# display_reva.net
KiCad netlist of a schematic drawn in EAGLE
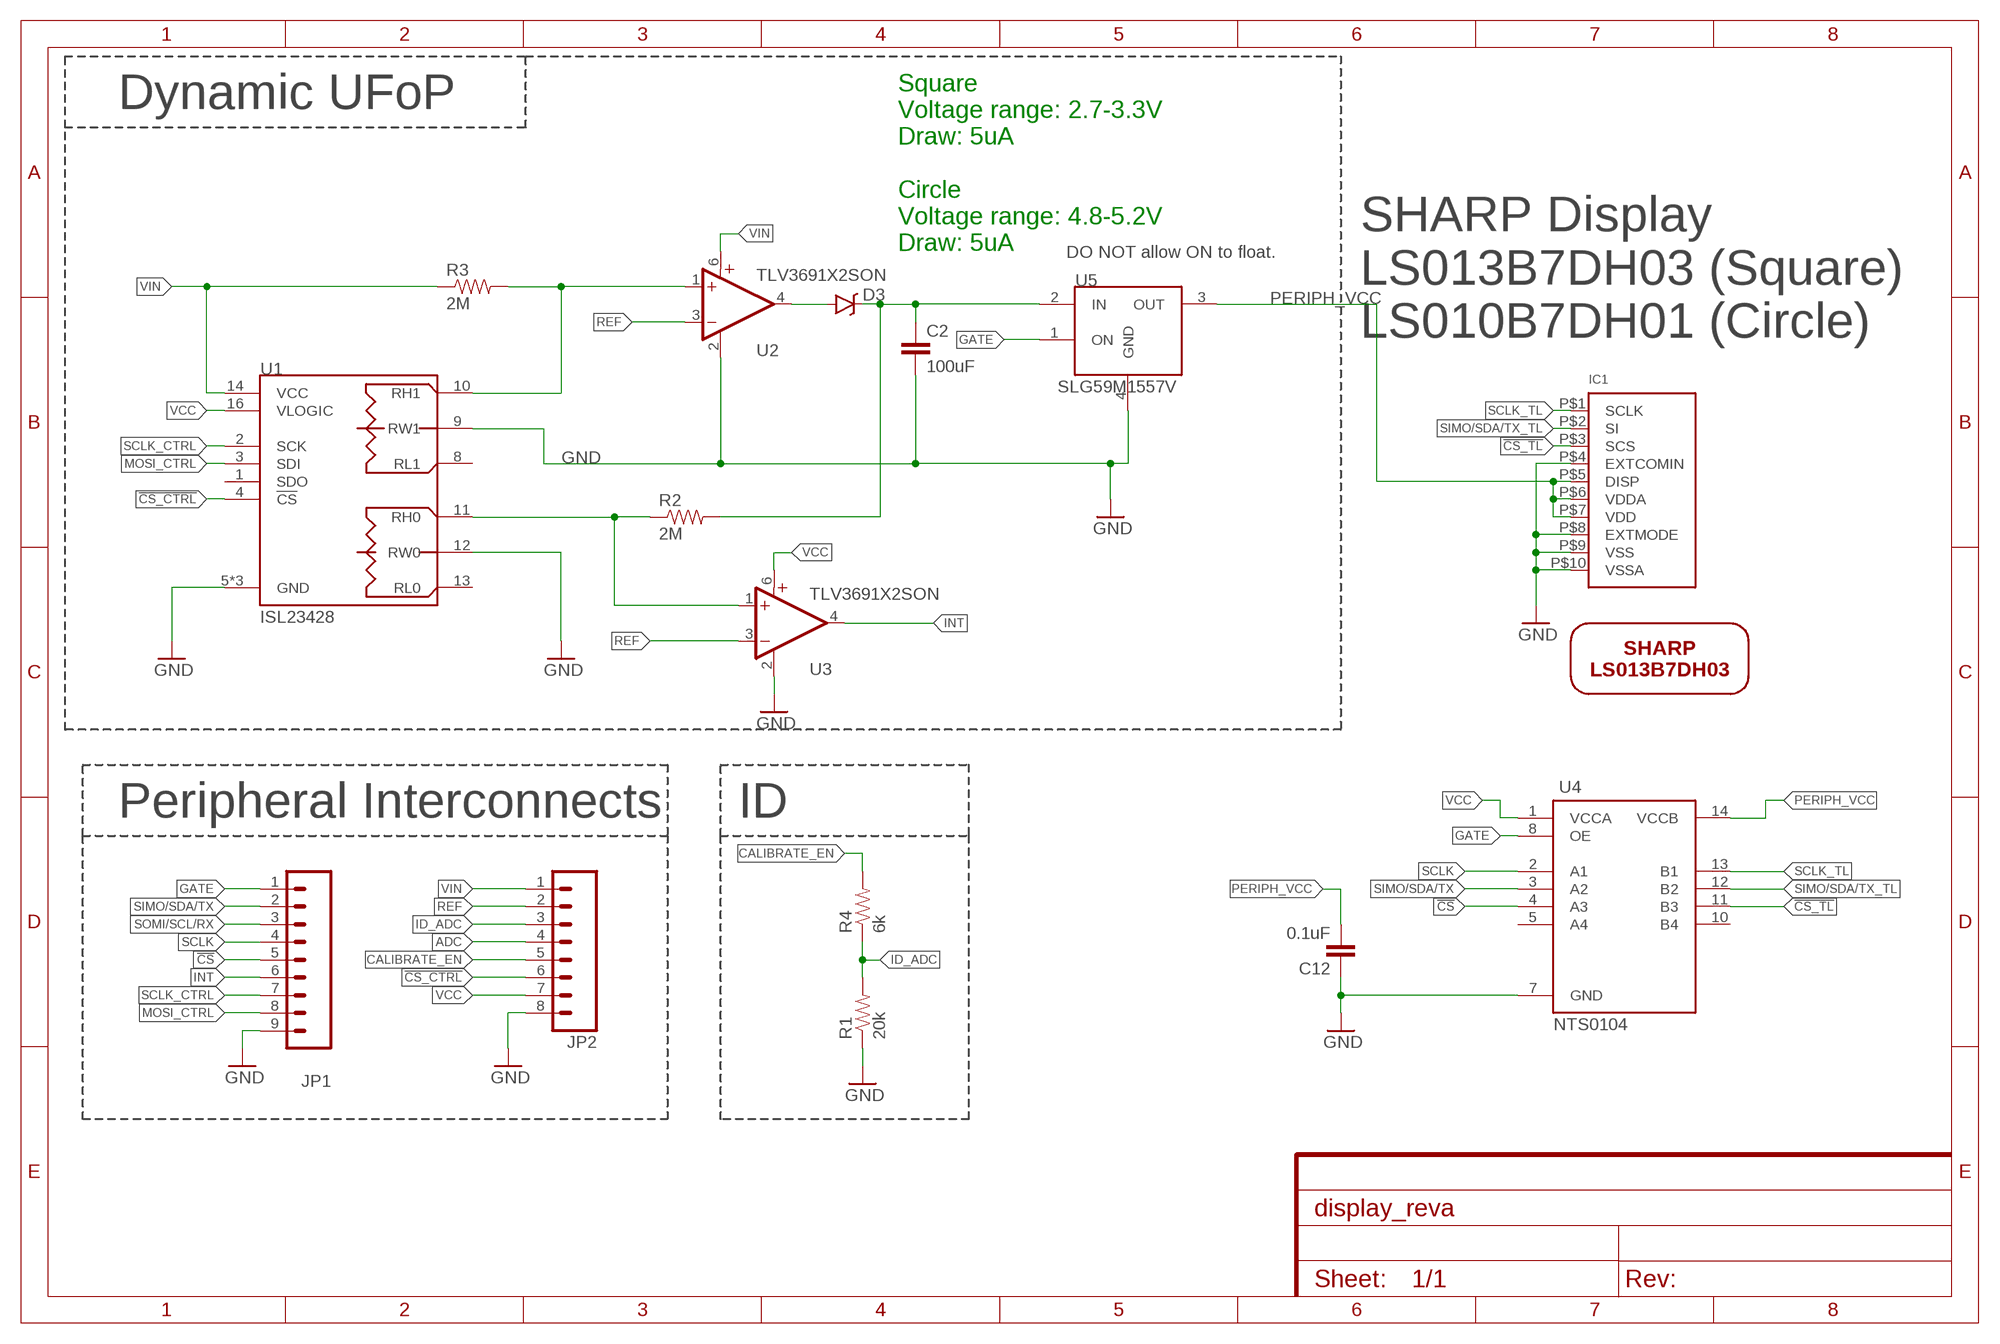
[diagram p0: schematic, sheet 1]

(export (version "E")
  (design (tool "Eeschema 10.0.6"))
  (components
    (comp (ref "C2")
      (value "100uF")
      (footprint "eagle-import:1206")
      (fields (field (name "MPN") "GRM31CR60J107ME39K"))
      (libsource (lib "eagle-import") (part "CAP1206"))
    )
    (comp (ref "C12")
      (value "0.1uF")
      (footprint "eagle-import:0402")
      (fields (field (name "MPN") "0402YD104KAT2A"))
      (libsource (lib "eagle-import") (part "C-EU"))
    )
    (comp (ref "D3")
      (value "RB751")
      (footprint "eagle-import:SOD-523")
      (fields (field (name "MPN") "BAS40-02V-V-G-08"))
      (libsource (lib "eagle-import") (part "DIODE-SCHOTTKY-RB751"))
    )
    (comp (ref "IC1")
      (value "SHARP_MEMORYLCD_10PIN")
      (footprint "eagle-import:FPC_10PIN_52892-1095")
      (fields (field (name "MPN") "0528921033"))
      (libsource (lib "eagle-import") (part "SHARP_MEMORYLCD_10PIN"))
    )
    (comp (ref "JP1")
      (value "M091.27MM")
      (footprint "eagle-import:1X09-1.27MM")
      (fields (field (name "MPN") "GRPB091VWVN-RC "))
      (libsource (lib "eagle-import") (part "M091.27MM"))
    )
    (comp (ref "JP2")
      (value "M081.27MM")
      (footprint "eagle-import:1X08-1.27MM")
      (fields (field (name "MPN") "GRPB081VWVN-RC "))
      (libsource (lib "eagle-import") (part "M081.27MM"))
    )
    (comp (ref "R1")
      (value "20k")
      (footprint "eagle-import:0402")
      (fields (field (name "MPN") "ERJ-2RKF2002X"))
      (libsource (lib "eagle-import") (part "R-EU"))
    )
    (comp (ref "R2")
      (value "2M")
      (footprint "eagle-import:0402")
      (fields (field (name "MPN") "RC1005F205CS"))
      (libsource (lib "eagle-import") (part "R-EU"))
    )
    (comp (ref "R3")
      (value "2M")
      (footprint "eagle-import:0402")
      (fields (field (name "MPN") "RC1005F205CS"))
      (libsource (lib "eagle-import") (part "R-EU"))
    )
    (comp (ref "R4")
      (value "6k")
      (footprint "eagle-import:0402")
      (fields (field (name "MPN") "RC0402FR-076K04L"))
      (libsource (lib "eagle-import") (part "R-EU"))
    )
    (comp (ref "U$3")
      (value "LS013B7DH03")
      (footprint "eagle-import:LS013B7DH03_HF")
      (libsource (lib "eagle-import") (part "LS013B7DH03"))
    )
    (comp (ref "U1")
      (value "ISL23428")
      (footprint "eagle-import:UTQFN-16")
      (fields (field (name "MPN") "ISL23428TFRUZ-T7A"))
      (libsource (lib "eagle-import") (part "ISL23428"))
    )
    (comp (ref "U2")
      (value "TLV3691X2SON")
      (footprint "eagle-import:X2SON")
      (fields (field (name "MPN") "TLV3691IDPFR"))
      (libsource (lib "eagle-import") (part "TLV3691X2SON"))
    )
    (comp (ref "U3")
      (value "TLV3691X2SON")
      (footprint "eagle-import:X2SON")
      (fields (field (name "MPN") "TLV3691IDPFR"))
      (libsource (lib "eagle-import") (part "TLV3691X2SON"))
    )
    (comp (ref "U4")
      (value "NTS0104")
      (footprint "eagle-import:TSSOP14")
      (fields (field (name "MANUFACTURERPARTNUMBER") "NTS0104PW,118 "))
      (libsource (lib "eagle-import") (part "NTS0104"))
    )
    (comp (ref "U5")
      (value "SLG59M1557V")
      (footprint "eagle-import:4STDFN")
      (fields (field (name "MPN") "SLG59M1557V "))
      (libsource (lib "eagle-import") (part "SLG59M1557V"))
    )
  )
  (nets
    (net (code "1") (name "/~{CS_CTRL}") (class "Default")
      (node (ref "JP2") (pin "6") (pinfunction "6_6") (pintype "passive"))
      (node (ref "U1") (pin "4") (pinfunction "~{CS}_4") (pintype "bidirectional"))
    )
    (net (code "2") (name "/~{CS_TL}") (class "Default")
      (node (ref "IC1") (pin "P$3") (pinfunction "SCS_P$3") (pintype "input"))
      (node (ref "U4") (pin "11") (pinfunction "B3_11") (pintype "bidirectional"))
    )
    (net (code "3") (name "/~{CS}") (class "Default")
      (node (ref "JP1") (pin "5") (pinfunction "5_5") (pintype "passive"))
      (node (ref "U4") (pin "4") (pinfunction "A3_4") (pintype "bidirectional"))
    )
    (net (code "4") (name "ADC") (class "Default")
      (node (ref "JP2") (pin "4") (pinfunction "4_4") (pintype "passive"))
    )
    (net (code "5") (name "CALIBRATE_EN") (class "Default")
      (node (ref "JP2") (pin "5") (pinfunction "5_5") (pintype "passive"))
      (node (ref "R4") (pin "2") (pinfunction "2_2") (pintype "passive"))
    )
    (net (code "6") (name "GATE") (class "Default")
      (node (ref "JP1") (pin "1") (pinfunction "1_1") (pintype "passive"))
      (node (ref "U4") (pin "8") (pinfunction "OE_8") (pintype "bidirectional"))
      (node (ref "U5") (pin "1") (pinfunction "ON_1") (pintype "bidirectional"))
    )
    (net (code "7") (name "GND") (class "Default")
      (node (ref "C12") (pin "1") (pinfunction "1_1") (pintype "passive"))
      (node (ref "C2") (pin "2") (pinfunction "2_2") (pintype "passive"))
      (node (ref "IC1") (pin "P$10") (pinfunction "VSSA_P$10") (pintype "power_in"))
      (node (ref "IC1") (pin "P$4") (pinfunction "EXTCOMIN_P$4") (pintype "input"))
      (node (ref "IC1") (pin "P$8") (pinfunction "EXTMODE_P$8") (pintype "input"))
      (node (ref "IC1") (pin "P$9") (pinfunction "VSS_P$9") (pintype "power_in"))
      (node (ref "JP1") (pin "9") (pinfunction "9_9") (pintype "passive"))
      (node (ref "JP2") (pin "8") (pinfunction "8_8") (pintype "passive"))
      (node (ref "R1") (pin "1") (pinfunction "1_1") (pintype "passive"))
      (node (ref "U1") (pin "12") (pinfunction "RW0_12") (pintype "bidirectional"))
      (node (ref "U1") (pin "15") (pinfunction "GND_15") (pintype "bidirectional"))
      (node (ref "U1") (pin "5") (pinfunction "GND_5") (pintype "bidirectional"))
      (node (ref "U1") (pin "6") (pinfunction "GND_6") (pintype "bidirectional"))
      (node (ref "U1") (pin "9") (pinfunction "RW1_9") (pintype "bidirectional"))
      (node (ref "U2") (pin "2") (pinfunction "GND_2") (pintype "power_in"))
      (node (ref "U3") (pin "2") (pinfunction "GND_2") (pintype "power_in"))
      (node (ref "U4") (pin "7") (pinfunction "GND_7") (pintype "bidirectional"))
      (node (ref "U5") (pin "4") (pinfunction "GND_4") (pintype "bidirectional"))
    )
    (net (code "8") (name "ID_ADC") (class "Default")
      (node (ref "JP2") (pin "3") (pinfunction "3_3") (pintype "passive"))
      (node (ref "R1") (pin "2") (pinfunction "2_2") (pintype "passive"))
      (node (ref "R4") (pin "1") (pinfunction "1_1") (pintype "passive"))
    )
    (net (code "9") (name "INT") (class "Default")
      (node (ref "JP1") (pin "6") (pinfunction "6_6") (pintype "passive"))
      (node (ref "U3") (pin "4") (pinfunction "OUT_4") (pintype "output"))
    )
    (net (code "10") (name "MOSI_CTRL") (class "Default")
      (node (ref "JP1") (pin "8") (pinfunction "8_8") (pintype "passive"))
      (node (ref "U1") (pin "3") (pinfunction "SDI_3") (pintype "bidirectional"))
    )
    (net (code "11") (name "Net-(U1-RH0)") (class "Default")
      (node (ref "R2") (pin "1") (pinfunction "1_1") (pintype "passive"))
      (node (ref "U1") (pin "11") (pinfunction "RH0_11") (pintype "bidirectional"))
      (node (ref "U3") (pin "1") (pinfunction "+IN_1") (pintype "input"))
    )
    (net (code "12") (name "Net-(U1-RH1)") (class "Default")
      (node (ref "R3") (pin "2") (pinfunction "2_2") (pintype "passive"))
      (node (ref "U1") (pin "10") (pinfunction "RH1_10") (pintype "bidirectional"))
      (node (ref "U2") (pin "1") (pinfunction "+IN_1") (pintype "input"))
    )
    (net (code "13") (name "Net-(U2-OUT)") (class "Default")
      (node (ref "D3") (pin "A") (pinfunction "A_A") (pintype "passive"))
      (node (ref "U2") (pin "4") (pinfunction "OUT_4") (pintype "output"))
    )
    (net (code "14") (name "Net-(U5-IN)") (class "Default")
      (node (ref "C2") (pin "1") (pinfunction "1_1") (pintype "passive"))
      (node (ref "D3") (pin "C") (pinfunction "C_C") (pintype "passive"))
      (node (ref "R2") (pin "2") (pinfunction "2_2") (pintype "passive"))
      (node (ref "U5") (pin "2") (pinfunction "IN_2") (pintype "bidirectional"))
    )
    (net (code "15") (name "PERIPH_VCC") (class "Default")
      (node (ref "C12") (pin "2") (pinfunction "2_2") (pintype "passive"))
      (node (ref "IC1") (pin "P$5") (pinfunction "DISP_P$5") (pintype "input"))
      (node (ref "IC1") (pin "P$6") (pinfunction "VDDA_P$6") (pintype "power_in"))
      (node (ref "IC1") (pin "P$7") (pinfunction "VDD_P$7") (pintype "power_in"))
      (node (ref "U4") (pin "14") (pinfunction "VCCB_14") (pintype "bidirectional"))
      (node (ref "U5") (pin "3") (pinfunction "OUT_3") (pintype "bidirectional"))
    )
    (net (code "16") (name "REF") (class "Default")
      (node (ref "JP2") (pin "2") (pinfunction "2_2") (pintype "passive"))
      (node (ref "U2") (pin "3") (pinfunction "-IN_3") (pintype "input"))
      (node (ref "U3") (pin "3") (pinfunction "-IN_3") (pintype "input"))
    )
    (net (code "17") (name "SCLK") (class "Default")
      (node (ref "JP1") (pin "4") (pinfunction "4_4") (pintype "passive"))
      (node (ref "U4") (pin "2") (pinfunction "A1_2") (pintype "bidirectional"))
    )
    (net (code "18") (name "SCLK_CTRL") (class "Default")
      (node (ref "JP1") (pin "7") (pinfunction "7_7") (pintype "passive"))
      (node (ref "U1") (pin "2") (pinfunction "SCK_2") (pintype "bidirectional"))
    )
    (net (code "19") (name "SCLK_TL") (class "Default")
      (node (ref "IC1") (pin "P$1") (pinfunction "SCLK_P$1") (pintype "input"))
      (node (ref "U4") (pin "13") (pinfunction "B1_13") (pintype "bidirectional"))
    )
    (net (code "20") (name "SIMO{slash}SDA{slash}TX") (class "Default")
      (node (ref "JP1") (pin "2") (pinfunction "2_2") (pintype "passive"))
      (node (ref "U4") (pin "3") (pinfunction "A2_3") (pintype "bidirectional"))
    )
    (net (code "21") (name "SIMO{slash}SDA{slash}TX_TL") (class "Default")
      (node (ref "IC1") (pin "P$2") (pinfunction "SI_P$2") (pintype "input"))
      (node (ref "U4") (pin "12") (pinfunction "B2_12") (pintype "bidirectional"))
    )
    (net (code "22") (name "SOMI{slash}SCL{slash}RX") (class "Default")
      (node (ref "JP1") (pin "3") (pinfunction "3_3") (pintype "passive"))
    )
    (net (code "23") (name "VCC") (class "Default")
      (node (ref "JP2") (pin "7") (pinfunction "7_7") (pintype "passive"))
      (node (ref "U1") (pin "16") (pinfunction "VLOGIC_16") (pintype "bidirectional"))
      (node (ref "U3") (pin "6") (pinfunction "V+_6") (pintype "power_in"))
      (node (ref "U4") (pin "1") (pinfunction "VCCA_1") (pintype "bidirectional"))
    )
    (net (code "24") (name "VIN") (class "Default")
      (node (ref "JP2") (pin "1") (pinfunction "1_1") (pintype "passive"))
      (node (ref "R3") (pin "1") (pinfunction "1_1") (pintype "passive"))
      (node (ref "U1") (pin "14") (pinfunction "VCC_14") (pintype "bidirectional"))
      (node (ref "U2") (pin "6") (pinfunction "V+_6") (pintype "power_in"))
    )
    (net (code "25") (name "unconnected-(U1-RL0-Pad13)") (class "Default")
      (node (ref "U1") (pin "13") (pinfunction "RL0_13") (pintype "bidirectional"))
    )
    (net (code "26") (name "unconnected-(U1-RL1-Pad8)") (class "Default")
      (node (ref "U1") (pin "8") (pinfunction "RL1_8") (pintype "bidirectional"))
    )
    (net (code "27") (name "unconnected-(U1-SDO-Pad1)") (class "Default")
      (node (ref "U1") (pin "1") (pinfunction "SDO_1") (pintype "bidirectional"))
    )
    (net (code "28") (name "unconnected-(U4-A4-Pad5)") (class "Default")
      (node (ref "U4") (pin "5") (pinfunction "A4_5") (pintype "bidirectional"))
    )
    (net (code "29") (name "unconnected-(U4-B4-Pad10)") (class "Default")
      (node (ref "U4") (pin "10") (pinfunction "B4_10") (pintype "bidirectional"))
    )
  )
)
